# mini_board0.net
KiCad netlist of a schematic drawn in EAGLE
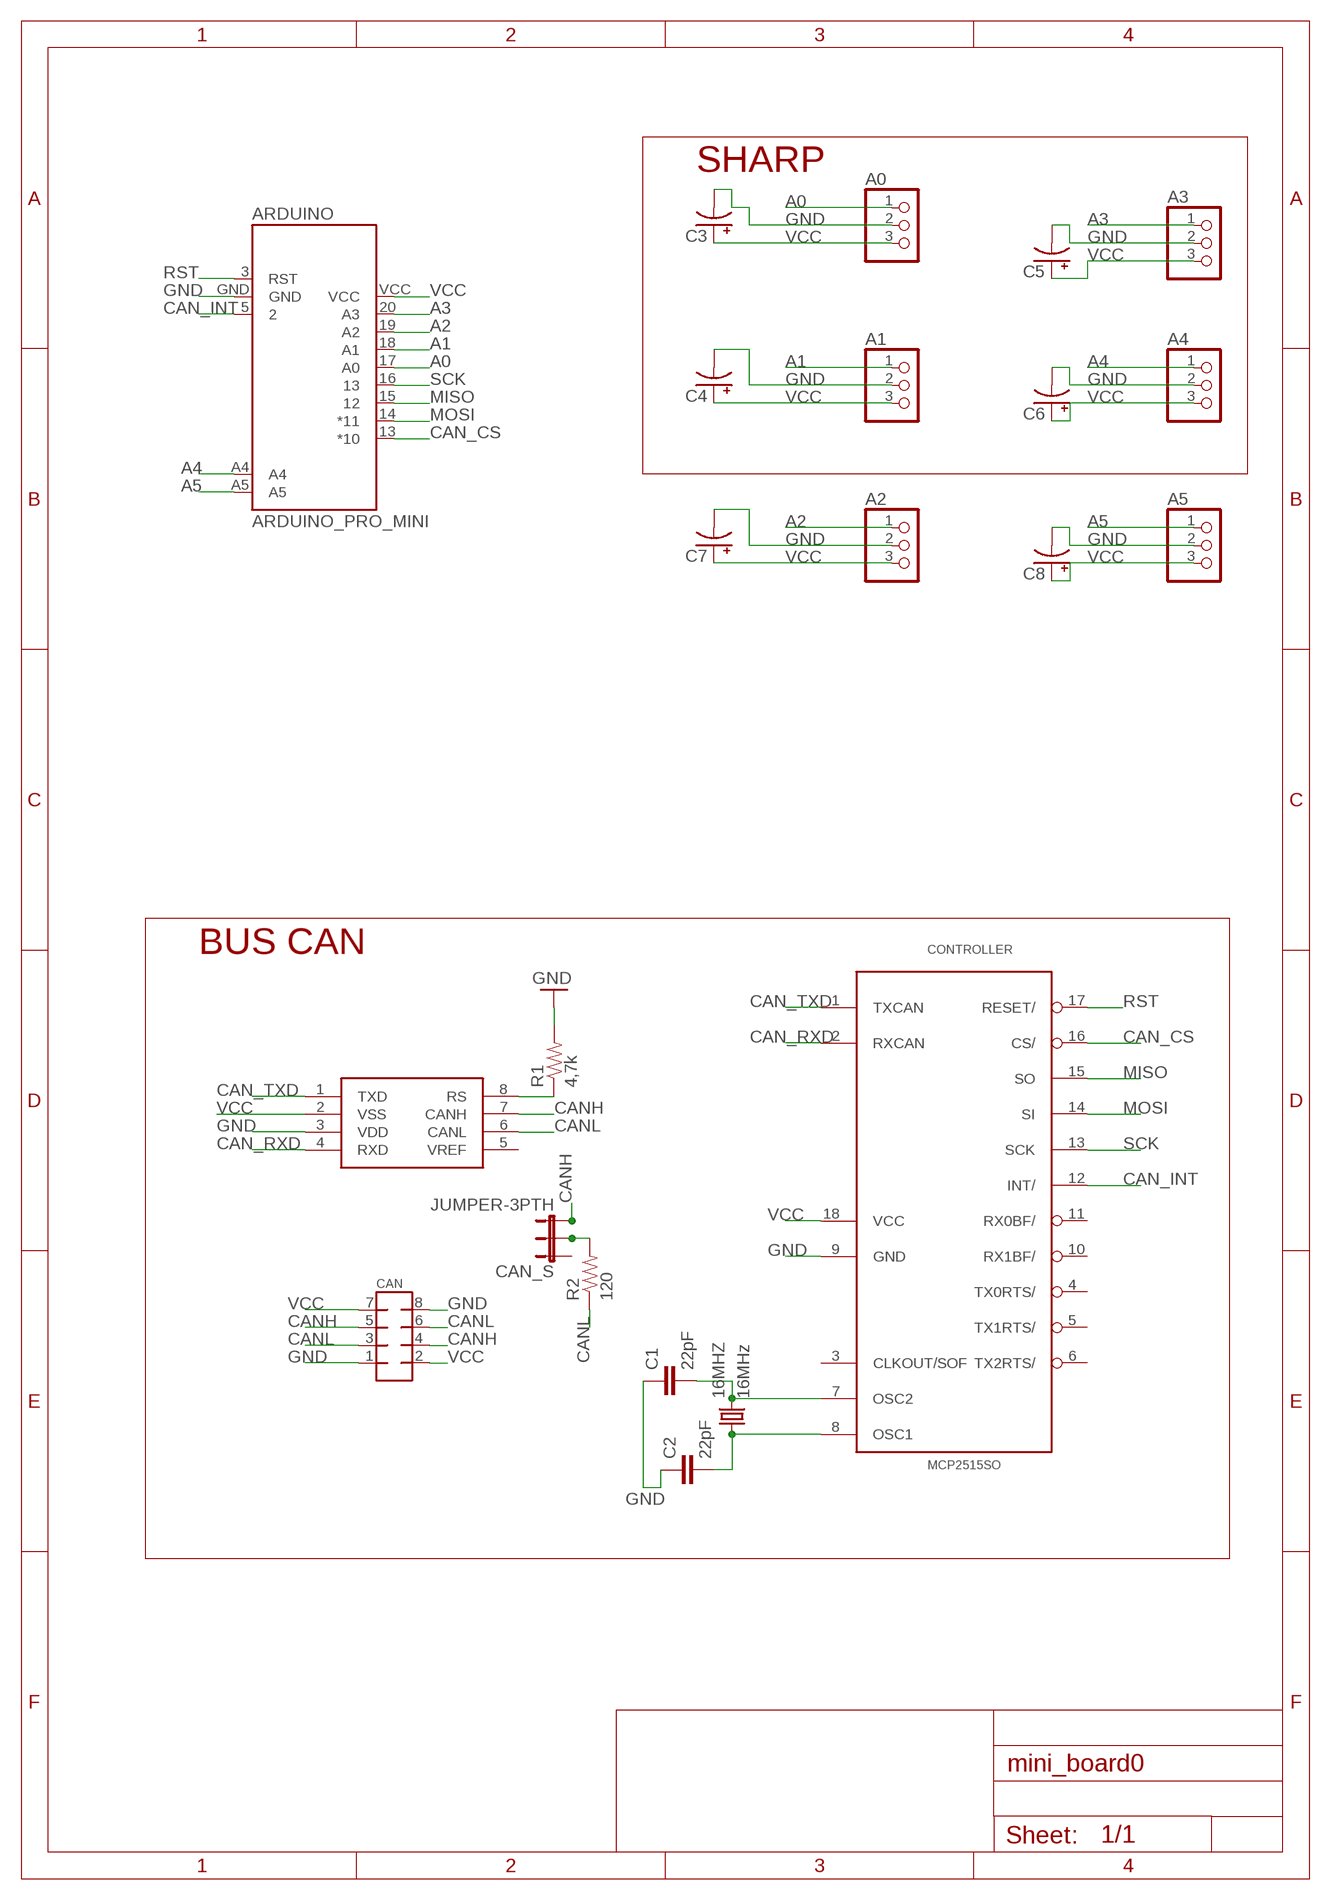
[diagram p0: schematic, sheet 1]

(export (version "E")
  (design (tool "Eeschema 10.0.6"))
  (components
    (comp (ref "16MHZ")
      (value "16MHz")
      (footprint "eagle-import:HC49_S")
      (libsource (lib "eagle-import") (part "CRYSTALHC49S"))
    )
    (comp (ref "A0")
      (value "PINHD-1X3/90")
      (footprint "eagle-import:1X03_90")
      (libsource (lib "eagle-import") (part "PINHD-1X3/90"))
    )
    (comp (ref "A1")
      (value "PINHD-1X3/90")
      (footprint "eagle-import:1X03_90")
      (libsource (lib "eagle-import") (part "PINHD-1X3/90"))
    )
    (comp (ref "A2")
      (value "PINHD-1X3/90")
      (footprint "eagle-import:1X03_90")
      (libsource (lib "eagle-import") (part "PINHD-1X3/90"))
    )
    (comp (ref "A3")
      (value "PINHD-1X3/90")
      (footprint "eagle-import:1X03_90")
      (libsource (lib "eagle-import") (part "PINHD-1X3/90"))
    )
    (comp (ref "A4")
      (value "PINHD-1X3/90")
      (footprint "eagle-import:1X03_90")
      (libsource (lib "eagle-import") (part "PINHD-1X3/90"))
    )
    (comp (ref "A5")
      (value "PINHD-1X3/90")
      (footprint "eagle-import:1X03_90")
      (libsource (lib "eagle-import") (part "PINHD-1X3/90"))
    )
    (comp (ref "ARDUINO")
      (value "ARDUINO_PRO_MINI")
      (footprint "eagle-import:ARDUINO_PRO_MINI")
      (libsource (lib "eagle-import") (part "ARDUINO_PRO_MINI"))
    )
    (comp (ref "C1")
      (value "22pF")
      (footprint "eagle-import:0805")
      (libsource (lib "eagle-import") (part "CAP0805"))
    )
    (comp (ref "C2")
      (value "22pF")
      (footprint "eagle-import:0805")
      (libsource (lib "eagle-import") (part "CAP0805"))
    )
    (comp (ref "C3")
      (value "CAP_POLPTH2")
      (footprint "eagle-import:CPOL-RADIAL-10UF-25V")
      (libsource (lib "eagle-import") (part "CAP_POLPTH2"))
    )
    (comp (ref "C4")
      (value "CAP_POLPTH2")
      (footprint "eagle-import:CPOL-RADIAL-10UF-25V")
      (libsource (lib "eagle-import") (part "CAP_POLPTH2"))
    )
    (comp (ref "C5")
      (value "CAP_POLPTH2")
      (footprint "eagle-import:CPOL-RADIAL-10UF-25V")
      (libsource (lib "eagle-import") (part "CAP_POLPTH2"))
    )
    (comp (ref "C6")
      (value "CAP_POLPTH2")
      (footprint "eagle-import:CPOL-RADIAL-10UF-25V")
      (libsource (lib "eagle-import") (part "CAP_POLPTH2"))
    )
    (comp (ref "C7")
      (value "CAP_POLPTH2")
      (footprint "eagle-import:CPOL-RADIAL-10UF-25V")
      (libsource (lib "eagle-import") (part "CAP_POLPTH2"))
    )
    (comp (ref "C8")
      (value "CAP_POLPTH2")
      (footprint "eagle-import:CPOL-RADIAL-10UF-25V")
      (libsource (lib "eagle-import") (part "CAP_POLPTH2"))
    )
    (comp (ref "CAN")
      (value "MMATCH-8-PTH")
      (footprint "eagle-import:AMP-215079-8")
      (libsource (lib "eagle-import") (part "MMATCH-8-PTH"))
    )
    (comp (ref "CAN_S")
      (value "JUMPER-3PTH")
      (footprint "eagle-import:1X03")
      (libsource (lib "eagle-import") (part "JUMPER-3PTH"))
    )
    (comp (ref "CONTROLLER")
      (value "MCP2515SO")
      (footprint "eagle-import:SO18L")
      (libsource (lib "eagle-import") (part "MCP2515SO"))
    )
    (comp (ref "R1")
      (value "4,7k")
      (footprint "eagle-import:0805")
      (libsource (lib "eagle-import") (part "RESISTOR0805-RES"))
    )
    (comp (ref "R2")
      (value "120")
      (footprint "eagle-import:0805")
      (libsource (lib "eagle-import") (part "RESISTOR0805-RES"))
    )
    (comp (ref "U1")
      (value "MCP2551")
      (footprint "eagle-import:SO08")
      (libsource (lib "eagle-import") (part "MCP2551"))
    )
  )
  (nets
    (net (code "1") (name "/A0") (class "Default")
      (node (ref "A0") (pin "1") (pinfunction "1_1") (pintype "passive"))
      (node (ref "ARDUINO") (pin "17") (pinfunction "A0_17") (pintype "bidirectional"))
    )
    (net (code "2") (name "/A1") (class "Default")
      (node (ref "A1") (pin "1") (pinfunction "1_1") (pintype "passive"))
      (node (ref "ARDUINO") (pin "18") (pinfunction "A1_18") (pintype "bidirectional"))
    )
    (net (code "3") (name "/A2") (class "Default")
      (node (ref "A2") (pin "1") (pinfunction "1_1") (pintype "passive"))
      (node (ref "ARDUINO") (pin "19") (pinfunction "A2_19") (pintype "bidirectional"))
    )
    (net (code "4") (name "/A3") (class "Default")
      (node (ref "A3") (pin "1") (pinfunction "1_1") (pintype "passive"))
      (node (ref "ARDUINO") (pin "20") (pinfunction "A3_20") (pintype "bidirectional"))
    )
    (net (code "5") (name "/A4") (class "Default")
      (node (ref "A4") (pin "1") (pinfunction "1_1") (pintype "passive"))
      (node (ref "ARDUINO") (pin "A4") (pinfunction "A4_A4") (pintype "bidirectional"))
    )
    (net (code "6") (name "/A5") (class "Default")
      (node (ref "A5") (pin "1") (pinfunction "1_1") (pintype "passive"))
      (node (ref "ARDUINO") (pin "A5") (pinfunction "A5_A5") (pintype "bidirectional"))
    )
    (net (code "7") (name "/CANH") (class "Default")
      (node (ref "CAN") (pin "4") (pinfunction "4_4") (pintype "bidirectional"))
      (node (ref "CAN") (pin "5") (pinfunction "5_5") (pintype "bidirectional"))
      (node (ref "CAN_S") (pin "3") (pinfunction "3_3") (pintype "passive"))
      (node (ref "U1") (pin "7") (pinfunction "CANH_7") (pintype "bidirectional"))
    )
    (net (code "8") (name "/CANL") (class "Default")
      (node (ref "CAN") (pin "3") (pinfunction "3_3") (pintype "bidirectional"))
      (node (ref "CAN") (pin "6") (pinfunction "6_6") (pintype "bidirectional"))
      (node (ref "R2") (pin "1") (pinfunction "1_1") (pintype "passive"))
      (node (ref "U1") (pin "6") (pinfunction "CANL_6") (pintype "bidirectional"))
    )
    (net (code "9") (name "/CAN_CS") (class "Default")
      (node (ref "ARDUINO") (pin "13") (pinfunction "*10_13") (pintype "bidirectional"))
      (node (ref "CONTROLLER") (pin "16") (pinfunction "CS/_16") (pintype "input"))
    )
    (net (code "10") (name "/CAN_INT") (class "Default")
      (node (ref "ARDUINO") (pin "5") (pinfunction "2_5") (pintype "bidirectional"))
      (node (ref "CONTROLLER") (pin "12") (pinfunction "INT/_12") (pintype "output"))
    )
    (net (code "11") (name "/CAN_RXD") (class "Default")
      (node (ref "CONTROLLER") (pin "2") (pinfunction "RXCAN_2") (pintype "input"))
      (node (ref "U1") (pin "4") (pinfunction "RXD_4") (pintype "bidirectional"))
    )
    (net (code "12") (name "/CAN_TXD") (class "Default")
      (node (ref "CONTROLLER") (pin "1") (pinfunction "TXCAN_1") (pintype "output"))
      (node (ref "U1") (pin "1") (pinfunction "TXD_1") (pintype "bidirectional"))
    )
    (net (code "13") (name "/MISO") (class "Default")
      (node (ref "ARDUINO") (pin "15") (pinfunction "12_15") (pintype "bidirectional"))
      (node (ref "CONTROLLER") (pin "15") (pinfunction "SO_15") (pintype "output"))
    )
    (net (code "14") (name "/MOSI") (class "Default")
      (node (ref "ARDUINO") (pin "14") (pinfunction "*11_14") (pintype "bidirectional"))
      (node (ref "CONTROLLER") (pin "14") (pinfunction "SI_14") (pintype "input"))
    )
    (net (code "15") (name "/RST") (class "Default")
      (node (ref "ARDUINO") (pin "3") (pinfunction "RST_3") (pintype "bidirectional"))
      (node (ref "CONTROLLER") (pin "17") (pinfunction "RESET/_17") (pintype "input"))
    )
    (net (code "16") (name "/SCK") (class "Default")
      (node (ref "ARDUINO") (pin "16") (pinfunction "13_16") (pintype "bidirectional"))
      (node (ref "CONTROLLER") (pin "13") (pinfunction "SCK_13") (pintype "input"))
    )
    (net (code "17") (name "/VCC") (class "Default")
      (node (ref "A0") (pin "3") (pinfunction "3_3") (pintype "passive"))
      (node (ref "A1") (pin "3") (pinfunction "3_3") (pintype "passive"))
      (node (ref "A2") (pin "3") (pinfunction "3_3") (pintype "passive"))
      (node (ref "A3") (pin "3") (pinfunction "3_3") (pintype "passive"))
      (node (ref "A4") (pin "3") (pinfunction "3_3") (pintype "passive"))
      (node (ref "A5") (pin "3") (pinfunction "3_3") (pintype "passive"))
      (node (ref "ARDUINO") (pin "VCC") (pinfunction "VCC_VCC") (pintype "bidirectional"))
      (node (ref "C3") (pin "1") (pinfunction "+_1") (pintype "passive"))
      (node (ref "C4") (pin "1") (pinfunction "+_1") (pintype "passive"))
      (node (ref "C5") (pin "1") (pinfunction "+_1") (pintype "passive"))
      (node (ref "C6") (pin "1") (pinfunction "+_1") (pintype "passive"))
      (node (ref "C7") (pin "1") (pinfunction "+_1") (pintype "passive"))
      (node (ref "C8") (pin "1") (pinfunction "+_1") (pintype "passive"))
      (node (ref "CAN") (pin "2") (pinfunction "2_2") (pintype "bidirectional"))
      (node (ref "CAN") (pin "7") (pinfunction "7_7") (pintype "bidirectional"))
      (node (ref "CONTROLLER") (pin "18") (pinfunction "VCC_18") (pintype "power_in"))
      (node (ref "U1") (pin "2") (pinfunction "VSS_2") (pintype "bidirectional"))
    )
    (net (code "18") (name "GND") (class "Default")
      (node (ref "A0") (pin "2") (pinfunction "2_2") (pintype "passive"))
      (node (ref "A1") (pin "2") (pinfunction "2_2") (pintype "passive"))
      (node (ref "A2") (pin "2") (pinfunction "2_2") (pintype "passive"))
      (node (ref "A3") (pin "2") (pinfunction "2_2") (pintype "passive"))
      (node (ref "A4") (pin "2") (pinfunction "2_2") (pintype "passive"))
      (node (ref "A5") (pin "2") (pinfunction "2_2") (pintype "passive"))
      (node (ref "ARDUINO") (pin "GND") (pinfunction "GND_GND") (pintype "bidirectional"))
      (node (ref "C1") (pin "1") (pinfunction "1_1") (pintype "passive"))
      (node (ref "C2") (pin "1") (pinfunction "1_1") (pintype "passive"))
      (node (ref "C3") (pin "2") (pinfunction "-_2") (pintype "passive"))
      (node (ref "C4") (pin "2") (pinfunction "-_2") (pintype "passive"))
      (node (ref "C5") (pin "2") (pinfunction "-_2") (pintype "passive"))
      (node (ref "C6") (pin "2") (pinfunction "-_2") (pintype "passive"))
      (node (ref "C7") (pin "2") (pinfunction "-_2") (pintype "passive"))
      (node (ref "C8") (pin "2") (pinfunction "-_2") (pintype "passive"))
      (node (ref "CAN") (pin "1") (pinfunction "1_1") (pintype "bidirectional"))
      (node (ref "CAN") (pin "8") (pinfunction "8_8") (pintype "bidirectional"))
      (node (ref "CONTROLLER") (pin "9") (pinfunction "GND_9") (pintype "power_in"))
      (node (ref "R1") (pin "2") (pinfunction "2_2") (pintype "passive"))
      (node (ref "U1") (pin "3") (pinfunction "VDD_3") (pintype "bidirectional"))
    )
    (net (code "19") (name "Net-(CAN_S-Pad2)") (class "Default")
      (node (ref "CAN_S") (pin "2") (pinfunction "2_2") (pintype "passive"))
      (node (ref "R2") (pin "2") (pinfunction "2_2") (pintype "passive"))
    )
    (net (code "20") (name "Net-(CONTROLLER-OSC1)") (class "Default")
      (node (ref "16MHZ") (pin "1") (pinfunction "1_1") (pintype "passive"))
      (node (ref "C2") (pin "2") (pinfunction "2_2") (pintype "passive"))
      (node (ref "CONTROLLER") (pin "8") (pinfunction "OSC1_8") (pintype "bidirectional"))
    )
    (net (code "21") (name "Net-(CONTROLLER-OSC2)") (class "Default")
      (node (ref "16MHZ") (pin "2") (pinfunction "2_2") (pintype "passive"))
      (node (ref "C1") (pin "2") (pinfunction "2_2") (pintype "passive"))
      (node (ref "CONTROLLER") (pin "7") (pinfunction "OSC2_7") (pintype "bidirectional"))
    )
    (net (code "22") (name "Net-(U1-RS)") (class "Default")
      (node (ref "R1") (pin "1") (pinfunction "1_1") (pintype "passive"))
      (node (ref "U1") (pin "8") (pinfunction "RS_8") (pintype "bidirectional"))
    )
    (net (code "23") (name "unconnected-(CAN_S-Pad1)") (class "Default")
      (node (ref "CAN_S") (pin "1") (pinfunction "1_1") (pintype "passive"))
    )
    (net (code "24") (name "unconnected-(CONTROLLER-CLKOUT{slash}SOF-Pad3)") (class "Default")
      (node (ref "CONTROLLER") (pin "3") (pinfunction "CLKOUT/SOF_3") (pintype "bidirectional"))
    )
    (net (code "25") (name "unconnected-(CONTROLLER-RX0BF{slash}-Pad11)") (class "Default")
      (node (ref "CONTROLLER") (pin "11") (pinfunction "RX0BF/_11") (pintype "bidirectional"))
    )
    (net (code "26") (name "unconnected-(CONTROLLER-RX1BF{slash}-Pad10)") (class "Default")
      (node (ref "CONTROLLER") (pin "10") (pinfunction "RX1BF/_10") (pintype "bidirectional"))
    )
    (net (code "27") (name "unconnected-(CONTROLLER-TX0RTS{slash}-Pad4)") (class "Default")
      (node (ref "CONTROLLER") (pin "4") (pinfunction "TX0RTS/_4") (pintype "bidirectional"))
    )
    (net (code "28") (name "unconnected-(CONTROLLER-TX1RTS{slash}-Pad5)") (class "Default")
      (node (ref "CONTROLLER") (pin "5") (pinfunction "TX1RTS/_5") (pintype "bidirectional"))
    )
    (net (code "29") (name "unconnected-(CONTROLLER-TX2RTS{slash}-Pad6)") (class "Default")
      (node (ref "CONTROLLER") (pin "6") (pinfunction "TX2RTS/_6") (pintype "bidirectional"))
    )
    (net (code "30") (name "unconnected-(U1-VREF-Pad5)") (class "Default")
      (node (ref "U1") (pin "5") (pinfunction "VREF_5") (pintype "bidirectional"))
    )
  )
)
